# AUTO_PROGRAMMING.net
KiCad netlist of a schematic drawn in Altium Designer
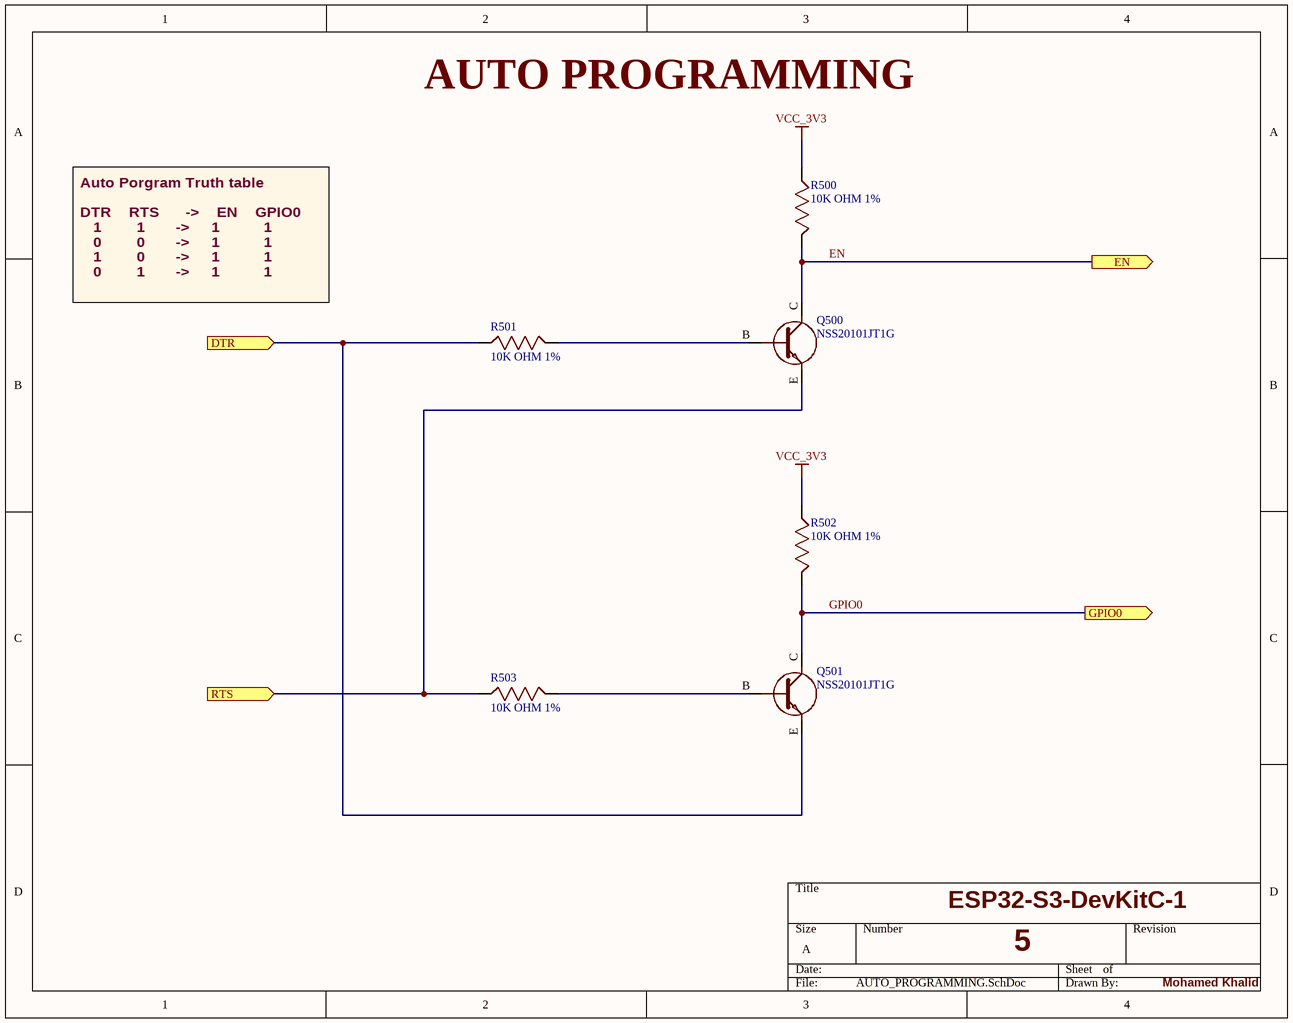
[diagram p0: AUTO_PROGRAMMING.SchDoc]

(export (version "E")
  (design (tool "Eeschema 10.0.6"))
  (components
    (comp (ref "Q500")
      (value "NSS20101JT1G")
      (footprint "SOTFL50P160X80-3N")
      (description "Bipolar Transistors - BJT 20V NPN LOW VCE(SAT)")
      (libsource (lib "ESP32_Integrated_Library") (part "NSS20101JT1G"))
    )
    (comp (ref "Q501")
      (value "NSS20101JT1G")
      (footprint "SOTFL50P160X80-3N")
      (description "Bipolar Transistors - BJT 20V NPN LOW VCE(SAT)")
      (libsource (lib "ESP32_Integrated_Library") (part "NSS20101JT1G"))
    )
    (comp (ref "R500")
      (value "10K OHM 1%")
      (footprint "RESC2012X65N")
      (description "10 kOhms ±1% 0.125W, 1/8W Chip Resistor 0805 (2012 Metric) Automotive AEC-Q200 Thick Film")
      (fields (field (name "TOLERANCE") "±1%"))
      (libsource (lib "ESP32_Integrated_Library") (part "RMCF0805FT10K0"))
    )
    (comp (ref "R501")
      (value "10K OHM 1%")
      (footprint "RESC2012X65N")
      (description "10 kOhms ±1% 0.125W, 1/8W Chip Resistor 0805 (2012 Metric) Automotive AEC-Q200 Thick Film")
      (fields (field (name "TOLERANCE") "±1%"))
      (libsource (lib "ESP32_Integrated_Library") (part "RMCF0805FT10K0"))
    )
    (comp (ref "R502")
      (value "10K OHM 1%")
      (footprint "RESC2012X65N")
      (description "10 kOhms ±1% 0.125W, 1/8W Chip Resistor 0805 (2012 Metric) Automotive AEC-Q200 Thick Film")
      (fields (field (name "TOLERANCE") "±1%"))
      (libsource (lib "ESP32_Integrated_Library") (part "RMCF0805FT10K0"))
    )
    (comp (ref "R503")
      (value "10K OHM 1%")
      (footprint "RESC2012X65N")
      (description "10 kOhms ±1% 0.125W, 1/8W Chip Resistor 0805 (2012 Metric) Automotive AEC-Q200 Thick Film")
      (fields (field (name "TOLERANCE") "±1%"))
      (libsource (lib "ESP32_Integrated_Library") (part "RMCF0805FT10K0"))
    )
  )
  (nets
    (net (code "1") (name "/DTR") (class "Default")
      (node (ref "Q501") (pin "E") (pinfunction "E_E") (pintype "passive"))
      (node (ref "R501") (pin "2") (pinfunction "2_2") (pintype "passive"))
    )
    (net (code "2") (name "/EN") (class "Default")
      (node (ref "Q500") (pin "C") (pinfunction "C_C") (pintype "passive"))
      (node (ref "R500") (pin "1") (pinfunction "1_1") (pintype "passive"))
    )
    (net (code "3") (name "/GPIO0") (class "Default")
      (node (ref "Q501") (pin "C") (pinfunction "C_C") (pintype "passive"))
      (node (ref "R502") (pin "1") (pinfunction "1_1") (pintype "passive"))
    )
    (net (code "4") (name "/RTS") (class "Default")
      (node (ref "Q500") (pin "E") (pinfunction "E_E") (pintype "passive"))
      (node (ref "R503") (pin "2") (pinfunction "2_2") (pintype "passive"))
    )
    (net (code "5") (name "Net-(Q500-PadB)") (class "Default")
      (node (ref "Q500") (pin "B") (pinfunction "B_B") (pintype "passive"))
      (node (ref "R501") (pin "1") (pinfunction "1_1") (pintype "passive"))
    )
    (net (code "6") (name "Net-(Q501-PadB)") (class "Default")
      (node (ref "Q501") (pin "B") (pinfunction "B_B") (pintype "passive"))
      (node (ref "R503") (pin "1") (pinfunction "1_1") (pintype "passive"))
    )
    (net (code "7") (name "VCC_3V3") (class "Default")
      (node (ref "R500") (pin "2") (pinfunction "2_2") (pintype "passive"))
      (node (ref "R502") (pin "2") (pinfunction "2_2") (pintype "passive"))
    )
  )
)
